# vraimenthorspcb.net
KiCad netlist of a schematic drawn in Altium Designer
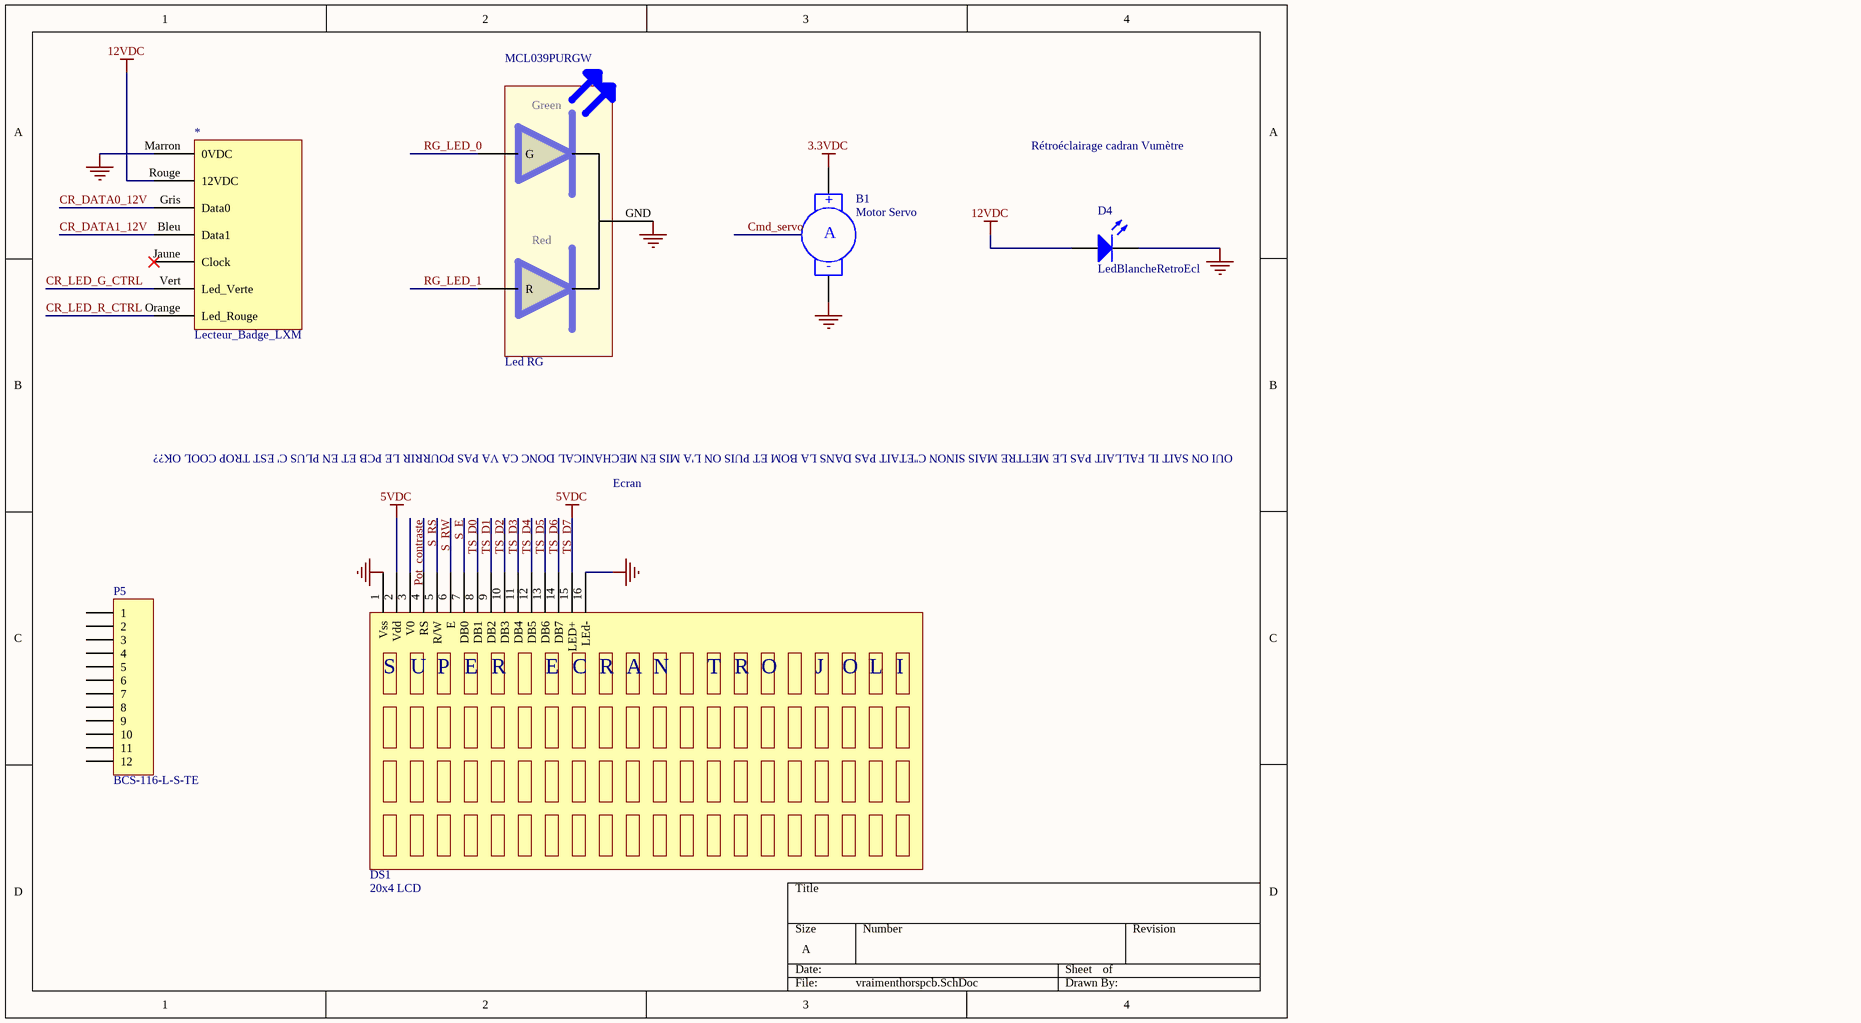
[diagram p0: vraimenthorspcb.SchDoc]

(export (version "E")
  (design (tool "Eeschema 10.0.6"))
  (components
    (comp (ref "*") (value "Lecteur_Badge_LXM") (libsource (lib "Schlib1") (part "Lecteur_Badge_LXM")))
    (comp (ref "B1")
      (value "Motor Servo")
      (footprint "RAD-0.4")
      (description "Servo Motor")
      (libsource (lib "Miscellaneous Devices") (part "Motor Servo"))
    )
    (comp (ref "D4")
      (value "LedBlancheRetroEcl")
      (footprint "LED-0")
      (description "LED Blanche retro vumetre")
      (libsource (lib "Miscellaneous Devices") (part "LED0"))
    )
    (comp (ref "DS1") (value "20x4 LCD") (libsource (lib "Schlib1") (part "MC42008A6W-FPTLW")))
    (comp (ref "MCL039PURGW") (value "Led RG") (libsource (lib "Schlib1") (part "MCL039PURGW")))
    (comp (ref "P5")
      (value "BCS-116-L-S-TE")
      (footprint "HDR1X12")
      (description "Header, 12-Pin")
      (libsource (lib "Miscellaneous Connectors") (part "Header 12"))
    )
  )
  (nets
    (net (code "1") (name "/CR_DATA0_12V") (class "Default")
      (node (ref "*") (pin "Gris") (pinfunction "Data0_Gris") (pintype "passive"))
    )
    (net (code "2") (name "/CR_DATA1_12V") (class "Default")
      (node (ref "*") (pin "Bleu") (pinfunction "Data1_Bleu") (pintype "passive"))
    )
    (net (code "3") (name "/CR_LED_G_CTRL") (class "Default")
      (node (ref "*") (pin "Vert") (pinfunction "Led_Verte_Vert") (pintype "passive"))
    )
    (net (code "4") (name "/CR_LED_R_CTRL") (class "Default")
      (node (ref "*") (pin "Orange") (pinfunction "Led_Rouge_Orange") (pintype "passive"))
    )
    (net (code "6") (name "/Pot_contraste") (class "Default")
      (node (ref "DS1") (pin "3") (pinfunction "V0_3") (pintype "passive"))
    )
    (net (code "7") (name "/RG_LED_0") (class "Default")
      (node (ref "MCL039PURGW") (pin "G") (pinfunction "G_G") (pintype "passive"))
    )
    (net (code "8") (name "/RG_LED_1") (class "Default")
      (node (ref "MCL039PURGW") (pin "R") (pinfunction "R_R") (pintype "passive"))
    )
    (net (code "9") (name "/S_E") (class "Default")
      (node (ref "DS1") (pin "6") (pinfunction "E_6") (pintype "passive"))
    )
    (net (code "10") (name "/S_RS") (class "Default")
      (node (ref "DS1") (pin "4") (pinfunction "RS_4") (pintype "passive"))
    )
    (net (code "11") (name "/S_RW") (class "Default")
      (node (ref "DS1") (pin "5") (pinfunction "R/W_5") (pintype "passive"))
    )
    (net (code "12") (name "/TS_D0") (class "Default")
      (node (ref "DS1") (pin "7") (pinfunction "DB0_7") (pintype "passive"))
    )
    (net (code "13") (name "/TS_D1") (class "Default")
      (node (ref "DS1") (pin "8") (pinfunction "DB1_8") (pintype "passive"))
    )
    (net (code "14") (name "/TS_D2") (class "Default")
      (node (ref "DS1") (pin "9") (pinfunction "DB2_9") (pintype "passive"))
    )
    (net (code "15") (name "/TS_D3") (class "Default")
      (node (ref "DS1") (pin "10") (pinfunction "DB3_10") (pintype "passive"))
    )
    (net (code "16") (name "/TS_D4") (class "Default")
      (node (ref "DS1") (pin "11") (pinfunction "DB4_11") (pintype "passive"))
    )
    (net (code "17") (name "/TS_D5") (class "Default")
      (node (ref "DS1") (pin "12") (pinfunction "DB5_12") (pintype "passive"))
    )
    (net (code "18") (name "/TS_D6") (class "Default")
      (node (ref "DS1") (pin "13") (pinfunction "DB6_13") (pintype "passive"))
    )
    (net (code "19") (name "/TS_D7") (class "Default")
      (node (ref "DS1") (pin "14") (pinfunction "DB7_14") (pintype "passive"))
    )
    (net (code "20") (name "3.3VDC") (class "Default")
      (node (ref "B1") (pin "1") (pinfunction "+_1") (pintype "passive"))
    )
    (net (code "21") (name "5VDC") (class "Default")
      (node (ref "DS1") (pin "15") (pinfunction "LED+_15") (pintype "passive"))
      (node (ref "DS1") (pin "2") (pinfunction "Vdd_2") (pintype "passive"))
    )
    (net (code "22") (name "12VDC") (class "Default")
      (node (ref "*") (pin "Rouge") (pinfunction "12VDC_Rouge") (pintype "passive"))
      (node (ref "D4") (pin "1") (pinfunction "A_1") (pintype "passive"))
    )
    (net (code "23") (name "GND") (class "Default")
      (node (ref "*") (pin "Marron") (pinfunction "0VDC_Marron") (pintype "passive"))
      (node (ref "B1") (pin "2") (pinfunction "-_2") (pintype "passive"))
      (node (ref "D4") (pin "2") (pinfunction "K_2") (pintype "passive"))
      (node (ref "DS1") (pin "1") (pinfunction "Vss_1") (pintype "passive"))
      (node (ref "DS1") (pin "16") (pinfunction "LEd-_16") (pintype "passive"))
      (node (ref "MCL039PURGW") (pin "GND") (pinfunction "GND_GND") (pintype "passive"))
    )
    (net (code "24") (name "unconnected-(*-Clock-PadJaune)") (class "Default")
      (node (ref "*") (pin "Jaune") (pinfunction "Clock_Jaune") (pintype "passive+no_connect"))
    )
    (net (code "25") (name "unconnected-(P5-Pad1)") (class "Default")
      (node (ref "P5") (pin "1") (pinfunction "1_1") (pintype "passive"))
    )
    (net (code "26") (name "unconnected-(P5-Pad2)") (class "Default")
      (node (ref "P5") (pin "2") (pinfunction "2_2") (pintype "passive"))
    )
    (net (code "27") (name "unconnected-(P5-Pad3)") (class "Default")
      (node (ref "P5") (pin "3") (pinfunction "3_3") (pintype "passive"))
    )
    (net (code "28") (name "unconnected-(P5-Pad4)") (class "Default")
      (node (ref "P5") (pin "4") (pinfunction "4_4") (pintype "passive"))
    )
    (net (code "29") (name "unconnected-(P5-Pad5)") (class "Default")
      (node (ref "P5") (pin "5") (pinfunction "5_5") (pintype "passive"))
    )
    (net (code "30") (name "unconnected-(P5-Pad6)") (class "Default")
      (node (ref "P5") (pin "6") (pinfunction "6_6") (pintype "passive"))
    )
    (net (code "31") (name "unconnected-(P5-Pad7)") (class "Default")
      (node (ref "P5") (pin "7") (pinfunction "7_7") (pintype "passive"))
    )
    (net (code "32") (name "unconnected-(P5-Pad8)") (class "Default")
      (node (ref "P5") (pin "8") (pinfunction "8_8") (pintype "passive"))
    )
    (net (code "33") (name "unconnected-(P5-Pad9)") (class "Default")
      (node (ref "P5") (pin "9") (pinfunction "9_9") (pintype "passive"))
    )
    (net (code "34") (name "unconnected-(P5-Pad10)") (class "Default")
      (node (ref "P5") (pin "10") (pinfunction "10_10") (pintype "passive"))
    )
    (net (code "35") (name "unconnected-(P5-Pad11)") (class "Default")
      (node (ref "P5") (pin "11") (pinfunction "11_11") (pintype "passive"))
    )
    (net (code "36") (name "unconnected-(P5-Pad12)") (class "Default")
      (node (ref "P5") (pin "12") (pinfunction "12_12") (pintype "passive"))
    )
  )
)
